# Main_board.net
KiCad netlist of a schematic drawn in EAGLE
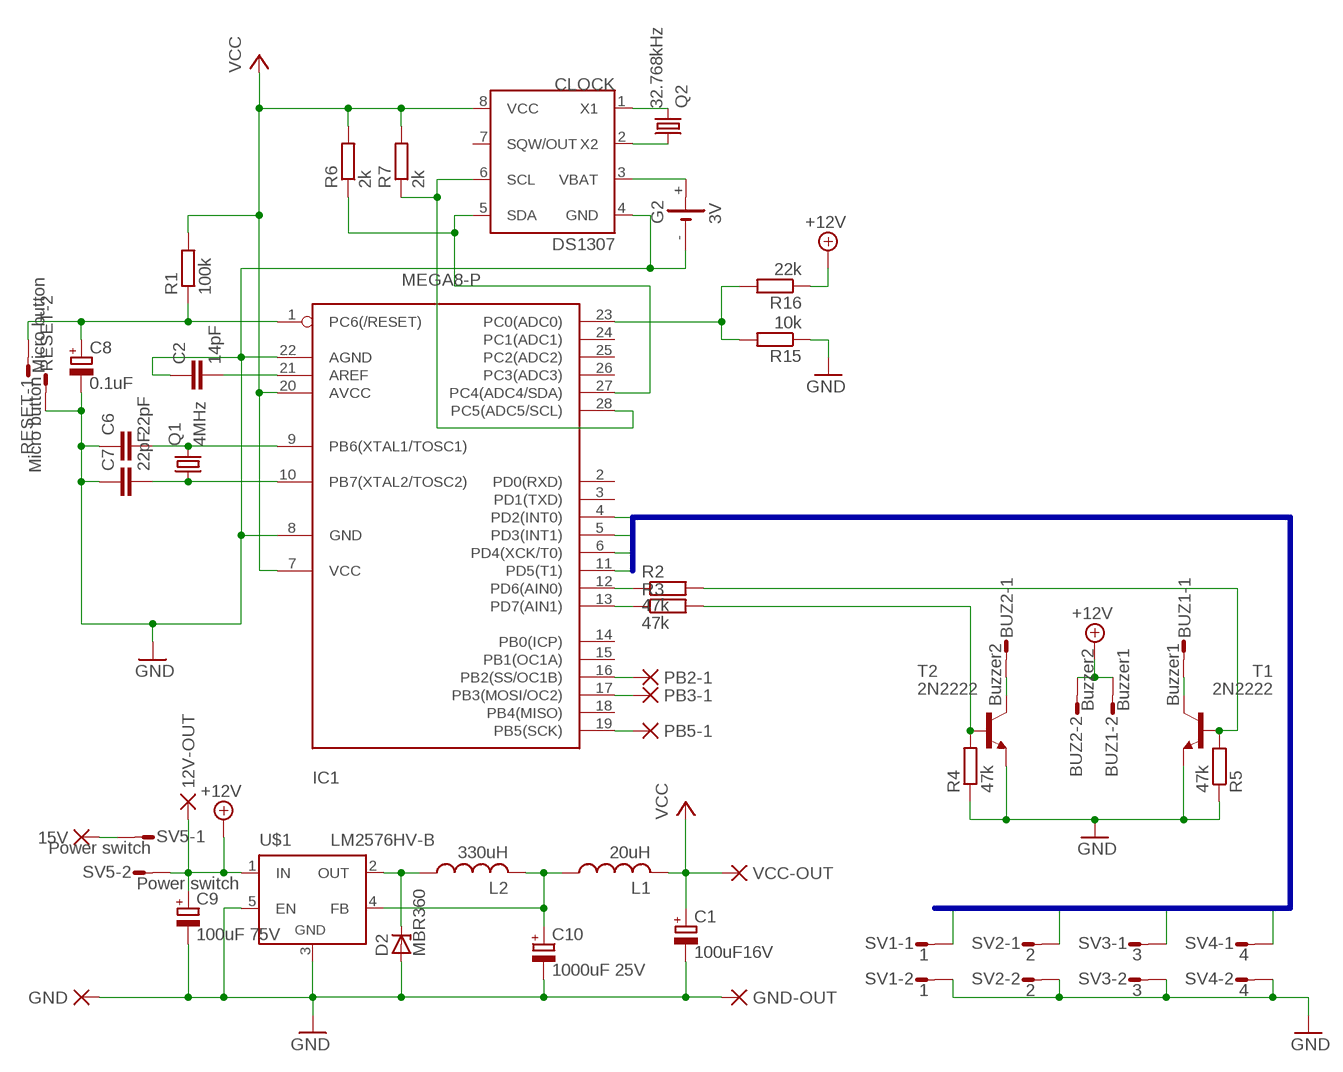
[diagram p0: schematic, sheet 1]

(export (version "E")
  (design (tool "Eeschema 10.0.6"))
  (components
    (comp (ref "12V-OUT")
      (value "PAD-0500")
      (footprint "eagle-import:0500")
      (libsource (lib "eagle-import") (part "PAD-0500"))
    )
    (comp (ref "15V")
      (value "PAD-0500")
      (footprint "eagle-import:0500")
      (libsource (lib "eagle-import") (part "PAD-0500"))
    )
    (comp (ref "BUZ1")
      (value "Buzzer1")
      (footprint "eagle-import:S02P")
      (libsource (lib "eagle-import") (part "S02P"))
    )
    (comp (ref "BUZ2")
      (value "Buzzer2")
      (footprint "eagle-import:S02P")
      (libsource (lib "eagle-import") (part "S02P"))
    )
    (comp (ref "C1")
      (value "100uF16V")
      (footprint "eagle-import:E2,5-6")
      (libsource (lib "eagle-import") (part "~~rcl_CPOL-EUE2.5-6"))
    )
    (comp (ref "C2")
      (value "14pF")
      (footprint "eagle-import:C025-050X050")
      (libsource (lib "eagle-import") (part "C-EU025-050X050"))
    )
    (comp (ref "C6")
      (value "22pF")
      (footprint "eagle-import:C025-030X050")
      (libsource (lib "eagle-import") (part "C-EU025-030X050"))
    )
    (comp (ref "C7")
      (value "22pF")
      (footprint "eagle-import:C025-030X050")
      (libsource (lib "eagle-import") (part "C-EU025-030X050"))
    )
    (comp (ref "C8")
      (value "0.1uF")
      (footprint "eagle-import:E2,5-6")
      (libsource (lib "eagle-import") (part "CPOL-EUE2.5-6"))
    )
    (comp (ref "C9")
      (value "100uF 75V")
      (footprint "eagle-import:E5-10,5")
      (libsource (lib "eagle-import") (part "~~rcl_CPOL-EUE5-10.5"))
    )
    (comp (ref "C10")
      (value "1000uF 25V")
      (footprint "eagle-import:E5-10,5")
      (libsource (lib "eagle-import") (part "~~rcl_CPOL-EUE5-10.5"))
    )
    (comp (ref "CLOCK")
      (value "DS1307")
      (footprint "eagle-import:SOIC-8")
      (libsource (lib "eagle-import") (part "DS1307"))
    )
    (comp (ref "D2")
      (value "MBR360")
      (footprint "eagle-import:C1702-15")
      (libsource (lib "eagle-import") (part "ZENER-DIODEC1702-15"))
    )
    (comp (ref "G2")
      (value "3V")
      (footprint "eagle-import:BEL_P")
      (libsource (lib "eagle-import") (part "SL-340/P"))
    )
    (comp (ref "GND")
      (value "PAD-0500")
      (footprint "eagle-import:0500")
      (libsource (lib "eagle-import") (part "PAD-0500"))
    )
    (comp (ref "GND-OUT")
      (value "PAD-0500")
      (footprint "eagle-import:0500")
      (libsource (lib "eagle-import") (part "PAD-0500"))
    )
    (comp (ref "IC1")
      (value "MEGA8-P")
      (footprint "eagle-import:DIL28-3")
      (libsource (lib "eagle-import") (part "MEGA8-P"))
    )
    (comp (ref "L1")
      (value "20uH")
      (footprint "eagle-import:TJ3-U1")
      (libsource (lib "eagle-import") (part "L-USTJ3-U1"))
    )
    (comp (ref "L2")
      (value "330uH")
      (footprint "eagle-import:TJ3-U1")
      (libsource (lib "eagle-import") (part "L-USTJ3-U1"))
    )
    (comp (ref "PB2-1")
      (value "PAD-0400")
      (footprint "eagle-import:0400")
      (libsource (lib "eagle-import") (part "PAD-0400"))
    )
    (comp (ref "PB3-1")
      (value "PAD-0400")
      (footprint "eagle-import:0400")
      (libsource (lib "eagle-import") (part "PAD-0400"))
    )
    (comp (ref "PB5-1")
      (value "PAD-0400")
      (footprint "eagle-import:0400")
      (libsource (lib "eagle-import") (part "PAD-0400"))
    )
    (comp (ref "Q1")
      (value "4MHz")
      (footprint "eagle-import:HC49U-V")
      (libsource (lib "eagle-import") (part "CRYSTALHC49U-V"))
    )
    (comp (ref "Q2")
      (value "32.768kHz")
      (footprint "eagle-import:CRYSTAL")
      (libsource (lib "eagle-import") (part "CRYSTAL"))
    )
    (comp (ref "R1")
      (value "100k")
      (footprint "eagle-import:0309_15")
      (libsource (lib "eagle-import") (part "R-EU_0309/15"))
    )
    (comp (ref "R2")
      (value "47k")
      (footprint "eagle-import:0309_15")
      (libsource (lib "eagle-import") (part "R-EU_0309/15"))
    )
    (comp (ref "R3")
      (value "47k")
      (footprint "eagle-import:0309_15")
      (libsource (lib "eagle-import") (part "R-EU_0309/15"))
    )
    (comp (ref "R4")
      (value "47k")
      (footprint "eagle-import:0309_15")
      (libsource (lib "eagle-import") (part "R-EU_0309/15"))
    )
    (comp (ref "R5")
      (value "47k")
      (footprint "eagle-import:0309_15")
      (libsource (lib "eagle-import") (part "R-EU_0309/15"))
    )
    (comp (ref "R6")
      (value "2k")
      (footprint "eagle-import:0309_15")
      (libsource (lib "eagle-import") (part "R-EU_0309/15"))
    )
    (comp (ref "R7")
      (value "2k")
      (footprint "eagle-import:0309_15")
      (libsource (lib "eagle-import") (part "R-EU_0309/15"))
    )
    (comp (ref "R15")
      (value "10k")
      (footprint "eagle-import:0309_15")
      (libsource (lib "eagle-import") (part "R-EU_0309/15"))
    )
    (comp (ref "R16")
      (value "22k")
      (footprint "eagle-import:0309_15")
      (libsource (lib "eagle-import") (part "R-EU_0309/15"))
    )
    (comp (ref "RESET")
      (value "Micro button")
      (footprint "eagle-import:S02P")
      (libsource (lib "eagle-import") (part "S02P"))
    )
    (comp (ref "SV1")
      (value "1")
      (footprint "eagle-import:S02P")
      (libsource (lib "eagle-import") (part "S02P"))
    )
    (comp (ref "SV2")
      (value "2")
      (footprint "eagle-import:S02P")
      (libsource (lib "eagle-import") (part "S02P"))
    )
    (comp (ref "SV3")
      (value "3")
      (footprint "eagle-import:S02P")
      (libsource (lib "eagle-import") (part "S02P"))
    )
    (comp (ref "SV4")
      (value "4")
      (footprint "eagle-import:S02P")
      (libsource (lib "eagle-import") (part "S02P"))
    )
    (comp (ref "SV5")
      (value "Power switch")
      (footprint "eagle-import:S02P")
      (libsource (lib "eagle-import") (part "S02P"))
    )
    (comp (ref "T1")
      (value "2N2222")
      (footprint "eagle-import:TO18")
      (libsource (lib "eagle-import") (part "2N2222"))
    )
    (comp (ref "T2")
      (value "2N2222")
      (footprint "eagle-import:TO18")
      (libsource (lib "eagle-import") (part "2N2222"))
    )
    (comp (ref "U$1")
      (value "LM2576HV-B")
      (footprint "eagle-import:TO220-53")
      (libsource (lib "eagle-import") (part "LM2576HV-B"))
    )
    (comp (ref "VCC-OUT")
      (value "PAD-0500")
      (footprint "eagle-import:0500")
      (libsource (lib "eagle-import") (part "PAD-0500"))
    )
  )
  (nets
    (net (code "1") (name "+12V") (class "Default")
      (node (ref "12V-OUT") (pin "P$1") (pinfunction "P_P$1") (pintype "passive"))
      (node (ref "BUZ1") (pin "2") (pinfunction "S_2") (pintype "passive"))
      (node (ref "BUZ2") (pin "2") (pinfunction "S_2") (pintype "passive"))
      (node (ref "C9") (pin "+") (pinfunction "+_+") (pintype "passive"))
      (node (ref "R16") (pin "1") (pinfunction "1_1") (pintype "passive"))
      (node (ref "SV5") (pin "2") (pinfunction "S_2") (pintype "passive"))
      (node (ref "U$1") (pin "1") (pinfunction "IN_1") (pintype "input"))
    )
    (net (code "2") (name "/INPUT1") (class "Default")
      (node (ref "IC1") (pin "4") (pinfunction "PD2(INT0)_4") (pintype "bidirectional"))
      (node (ref "SV1") (pin "1") (pinfunction "S_1") (pintype "passive"))
    )
    (net (code "3") (name "/INPUT2") (class "Default")
      (node (ref "IC1") (pin "5") (pinfunction "PD3(INT1)_5") (pintype "bidirectional"))
      (node (ref "SV2") (pin "1") (pinfunction "S_1") (pintype "passive"))
    )
    (net (code "4") (name "/INPUT3") (class "Default")
      (node (ref "IC1") (pin "6") (pinfunction "PD4(XCK/T0)_6") (pintype "bidirectional"))
      (node (ref "SV3") (pin "1") (pinfunction "S_1") (pintype "passive"))
    )
    (net (code "5") (name "/INPUT4") (class "Default")
      (node (ref "IC1") (pin "11") (pinfunction "PD5(T1)_11") (pintype "bidirectional"))
      (node (ref "SV4") (pin "1") (pinfunction "S_1") (pintype "passive"))
    )
    (net (code "6") (name "GND") (class "Default")
      (node (ref "C1") (pin "-") (pinfunction "-_-") (pintype "passive"))
      (node (ref "C10") (pin "-") (pinfunction "-_-") (pintype "passive"))
      (node (ref "C2") (pin "1") (pinfunction "1_1") (pintype "passive"))
      (node (ref "C6") (pin "1") (pinfunction "1_1") (pintype "passive"))
      (node (ref "C7") (pin "1") (pinfunction "1_1") (pintype "passive"))
      (node (ref "C8") (pin "-") (pinfunction "-_-") (pintype "passive"))
      (node (ref "C9") (pin "-") (pinfunction "-_-") (pintype "passive"))
      (node (ref "CLOCK") (pin "4") (pinfunction "GND_4") (pintype "power_in"))
      (node (ref "D2") (pin "A") (pinfunction "A_A") (pintype "passive"))
      (node (ref "G2") (pin "-") (pinfunction "-_-") (pintype "passive"))
      (node (ref "GND") (pin "P$1") (pinfunction "P_P$1") (pintype "passive"))
      (node (ref "GND-OUT") (pin "P$1") (pinfunction "P_P$1") (pintype "passive"))
      (node (ref "IC1") (pin "22") (pinfunction "AGND_22") (pintype "power_in"))
      (node (ref "IC1") (pin "8") (pinfunction "GND_8") (pintype "power_in"))
      (node (ref "R15") (pin "1") (pinfunction "1_1") (pintype "passive"))
      (node (ref "R4") (pin "1") (pinfunction "1_1") (pintype "passive"))
      (node (ref "R5") (pin "1") (pinfunction "1_1") (pintype "passive"))
      (node (ref "RESET") (pin "2") (pinfunction "S_2") (pintype "passive"))
      (node (ref "SV1") (pin "2") (pinfunction "S_2") (pintype "passive"))
      (node (ref "SV2") (pin "2") (pinfunction "S_2") (pintype "passive"))
      (node (ref "SV3") (pin "2") (pinfunction "S_2") (pintype "passive"))
      (node (ref "SV4") (pin "2") (pinfunction "S_2") (pintype "passive"))
      (node (ref "T1") (pin "1") (pinfunction "E_1") (pintype "passive"))
      (node (ref "T2") (pin "1") (pinfunction "E_1") (pintype "passive"))
      (node (ref "U$1") (pin "3") (pinfunction "GND_3") (pintype "power_in"))
      (node (ref "U$1") (pin "5") (pinfunction "EN_5") (pintype "input"))
    )
    (net (code "7") (name "Net-(15V-P)") (class "Default")
      (node (ref "15V") (pin "P$1") (pinfunction "P_P$1") (pintype "passive"))
      (node (ref "SV5") (pin "1") (pinfunction "S_1") (pintype "passive"))
    )
    (net (code "8") (name "Net-(BUZ1A-S)") (class "Default")
      (node (ref "BUZ1") (pin "1") (pinfunction "S_1") (pintype "passive"))
      (node (ref "T1") (pin "3") (pinfunction "C_3") (pintype "passive"))
    )
    (net (code "9") (name "Net-(BUZ2A-S)") (class "Default")
      (node (ref "BUZ2") (pin "1") (pinfunction "S_1") (pintype "passive"))
      (node (ref "T2") (pin "3") (pinfunction "C_3") (pintype "passive"))
    )
    (net (code "10") (name "Net-(CLOCK-SCL)") (class "Default")
      (node (ref "CLOCK") (pin "6") (pinfunction "SCL_6") (pintype "input"))
      (node (ref "IC1") (pin "28") (pinfunction "PC5(ADC5/SCL)_28") (pintype "bidirectional"))
      (node (ref "R7") (pin "1") (pinfunction "1_1") (pintype "passive"))
    )
    (net (code "11") (name "Net-(CLOCK-SDA)") (class "Default")
      (node (ref "CLOCK") (pin "5") (pinfunction "SDA_5") (pintype "bidirectional"))
      (node (ref "IC1") (pin "27") (pinfunction "PC4(ADC4/SDA)_27") (pintype "bidirectional"))
      (node (ref "R6") (pin "1") (pinfunction "1_1") (pintype "passive"))
    )
    (net (code "12") (name "Net-(CLOCK-VBAT)") (class "Default")
      (node (ref "CLOCK") (pin "3") (pinfunction "VBAT_3") (pintype "power_in"))
      (node (ref "G2") (pin "+") (pinfunction "+_+") (pintype "passive"))
    )
    (net (code "13") (name "Net-(CLOCK-X1)") (class "Default")
      (node (ref "CLOCK") (pin "1") (pinfunction "X1_1") (pintype "input"))
      (node (ref "Q2") (pin "2") (pinfunction "2_2") (pintype "passive"))
    )
    (net (code "14") (name "Net-(CLOCK-X2)") (class "Default")
      (node (ref "CLOCK") (pin "2") (pinfunction "X2_2") (pintype "output"))
      (node (ref "Q2") (pin "1") (pinfunction "1_1") (pintype "passive"))
    )
    (net (code "15") (name "Net-(IC1-AREF)") (class "Default")
      (node (ref "C2") (pin "2") (pinfunction "2_2") (pintype "passive"))
      (node (ref "IC1") (pin "21") (pinfunction "AREF_21") (pintype "passive"))
    )
    (net (code "16") (name "Net-(IC1-PB2(SS{slash}OC1B))") (class "Default")
      (node (ref "IC1") (pin "16") (pinfunction "PB2(SS/OC1B)_16") (pintype "bidirectional"))
      (node (ref "PB2-1") (pin "P$1") (pinfunction "P_P$1") (pintype "passive"))
    )
    (net (code "17") (name "Net-(IC1-PB3(MOSI{slash}OC2))") (class "Default")
      (node (ref "IC1") (pin "17") (pinfunction "PB3(MOSI/OC2)_17") (pintype "bidirectional"))
      (node (ref "PB3-1") (pin "P$1") (pinfunction "P_P$1") (pintype "passive"))
    )
    (net (code "18") (name "Net-(IC1-PB5(SCK))") (class "Default")
      (node (ref "IC1") (pin "19") (pinfunction "PB5(SCK)_19") (pintype "bidirectional"))
      (node (ref "PB5-1") (pin "P$1") (pinfunction "P_P$1") (pintype "passive"))
    )
    (net (code "19") (name "Net-(IC1-PB6(XTAL1{slash}TOSC1))") (class "Default")
      (node (ref "C6") (pin "2") (pinfunction "2_2") (pintype "passive"))
      (node (ref "IC1") (pin "9") (pinfunction "PB6(XTAL1/TOSC1)_9") (pintype "bidirectional"))
      (node (ref "Q1") (pin "2") (pinfunction "2_2") (pintype "passive"))
    )
    (net (code "20") (name "Net-(IC1-PB7(XTAL2{slash}TOSC2))") (class "Default")
      (node (ref "C7") (pin "2") (pinfunction "2_2") (pintype "passive"))
      (node (ref "IC1") (pin "10") (pinfunction "PB7(XTAL2/TOSC2)_10") (pintype "bidirectional"))
      (node (ref "Q1") (pin "1") (pinfunction "1_1") (pintype "passive"))
    )
    (net (code "21") (name "Net-(IC1-PC0(ADC0))") (class "Default")
      (node (ref "IC1") (pin "23") (pinfunction "PC0(ADC0)_23") (pintype "bidirectional"))
      (node (ref "R15") (pin "2") (pinfunction "2_2") (pintype "passive"))
      (node (ref "R16") (pin "2") (pinfunction "2_2") (pintype "passive"))
    )
    (net (code "22") (name "Net-(IC1-PC6({slash}RESET))") (class "Default")
      (node (ref "C8") (pin "+") (pinfunction "+_+") (pintype "passive"))
      (node (ref "IC1") (pin "1") (pinfunction "PC6(/RESET)_1") (pintype "bidirectional"))
      (node (ref "R1") (pin "1") (pinfunction "1_1") (pintype "passive"))
      (node (ref "RESET") (pin "1") (pinfunction "S_1") (pintype "passive"))
    )
    (net (code "23") (name "Net-(IC1-PD6(AIN0))") (class "Default")
      (node (ref "IC1") (pin "12") (pinfunction "PD6(AIN0)_12") (pintype "bidirectional"))
      (node (ref "R2") (pin "1") (pinfunction "1_1") (pintype "passive"))
    )
    (net (code "24") (name "Net-(IC1-PD7(AIN1))") (class "Default")
      (node (ref "IC1") (pin "13") (pinfunction "PD7(AIN1)_13") (pintype "bidirectional"))
      (node (ref "R3") (pin "1") (pinfunction "1_1") (pintype "passive"))
    )
    (net (code "25") (name "Net-(T1-B)") (class "Default")
      (node (ref "R2") (pin "2") (pinfunction "2_2") (pintype "passive"))
      (node (ref "R5") (pin "2") (pinfunction "2_2") (pintype "passive"))
      (node (ref "T1") (pin "2") (pinfunction "B_2") (pintype "passive"))
    )
    (net (code "26") (name "Net-(T2-B)") (class "Default")
      (node (ref "R3") (pin "2") (pinfunction "2_2") (pintype "passive"))
      (node (ref "R4") (pin "2") (pinfunction "2_2") (pintype "passive"))
      (node (ref "T2") (pin "2") (pinfunction "B_2") (pintype "passive"))
    )
    (net (code "27") (name "Net-(U$1-FB)") (class "Default")
      (node (ref "C10") (pin "+") (pinfunction "+_+") (pintype "passive"))
      (node (ref "L1") (pin "1") (pinfunction "1_1") (pintype "passive"))
      (node (ref "L2") (pin "2") (pinfunction "2_2") (pintype "passive"))
      (node (ref "U$1") (pin "4") (pinfunction "FB_4") (pintype "input"))
    )
    (net (code "28") (name "Net-(U$1-OUT)") (class "Default")
      (node (ref "D2") (pin "C") (pinfunction "C_C") (pintype "passive"))
      (node (ref "L2") (pin "1") (pinfunction "1_1") (pintype "passive"))
      (node (ref "U$1") (pin "2") (pinfunction "OUT_2") (pintype "output"))
    )
    (net (code "29") (name "VCC") (class "Default")
      (node (ref "C1") (pin "+") (pinfunction "+_+") (pintype "passive"))
      (node (ref "CLOCK") (pin "8") (pinfunction "VCC_8") (pintype "power_in"))
      (node (ref "IC1") (pin "20") (pinfunction "AVCC_20") (pintype "power_in"))
      (node (ref "IC1") (pin "7") (pinfunction "VCC_7") (pintype "power_in"))
      (node (ref "L1") (pin "2") (pinfunction "2_2") (pintype "passive"))
      (node (ref "R1") (pin "2") (pinfunction "2_2") (pintype "passive"))
      (node (ref "R6") (pin "2") (pinfunction "2_2") (pintype "passive"))
      (node (ref "R7") (pin "2") (pinfunction "2_2") (pintype "passive"))
      (node (ref "VCC-OUT") (pin "P$1") (pinfunction "P_P$1") (pintype "passive"))
    )
    (net (code "30") (name "unconnected-(CLOCK-SQW{slash}OUT-Pad7)") (class "Default")
      (node (ref "CLOCK") (pin "7") (pinfunction "SQW/OUT_7") (pintype "output"))
    )
    (net (code "31") (name "unconnected-(IC1-PB0(ICP)-Pad14)") (class "Default")
      (node (ref "IC1") (pin "14") (pinfunction "PB0(ICP)_14") (pintype "bidirectional"))
    )
    (net (code "32") (name "unconnected-(IC1-PB1(OC1A)-Pad15)") (class "Default")
      (node (ref "IC1") (pin "15") (pinfunction "PB1(OC1A)_15") (pintype "bidirectional"))
    )
    (net (code "33") (name "unconnected-(IC1-PB4(MISO)-Pad18)") (class "Default")
      (node (ref "IC1") (pin "18") (pinfunction "PB4(MISO)_18") (pintype "bidirectional"))
    )
    (net (code "34") (name "unconnected-(IC1-PC1(ADC1)-Pad24)") (class "Default")
      (node (ref "IC1") (pin "24") (pinfunction "PC1(ADC1)_24") (pintype "bidirectional"))
    )
    (net (code "35") (name "unconnected-(IC1-PC2(ADC2)-Pad25)") (class "Default")
      (node (ref "IC1") (pin "25") (pinfunction "PC2(ADC2)_25") (pintype "bidirectional"))
    )
    (net (code "36") (name "unconnected-(IC1-PC3(ADC3)-Pad26)") (class "Default")
      (node (ref "IC1") (pin "26") (pinfunction "PC3(ADC3)_26") (pintype "bidirectional"))
    )
    (net (code "37") (name "unconnected-(IC1-PD0(RXD)-Pad2)") (class "Default")
      (node (ref "IC1") (pin "2") (pinfunction "PD0(RXD)_2") (pintype "bidirectional"))
    )
    (net (code "38") (name "unconnected-(IC1-PD1(TXD)-Pad3)") (class "Default")
      (node (ref "IC1") (pin "3") (pinfunction "PD1(TXD)_3") (pintype "bidirectional"))
    )
  )
)
